# clock_led_switches.net
KiCad netlist of a schematic drawn in Altium Designer
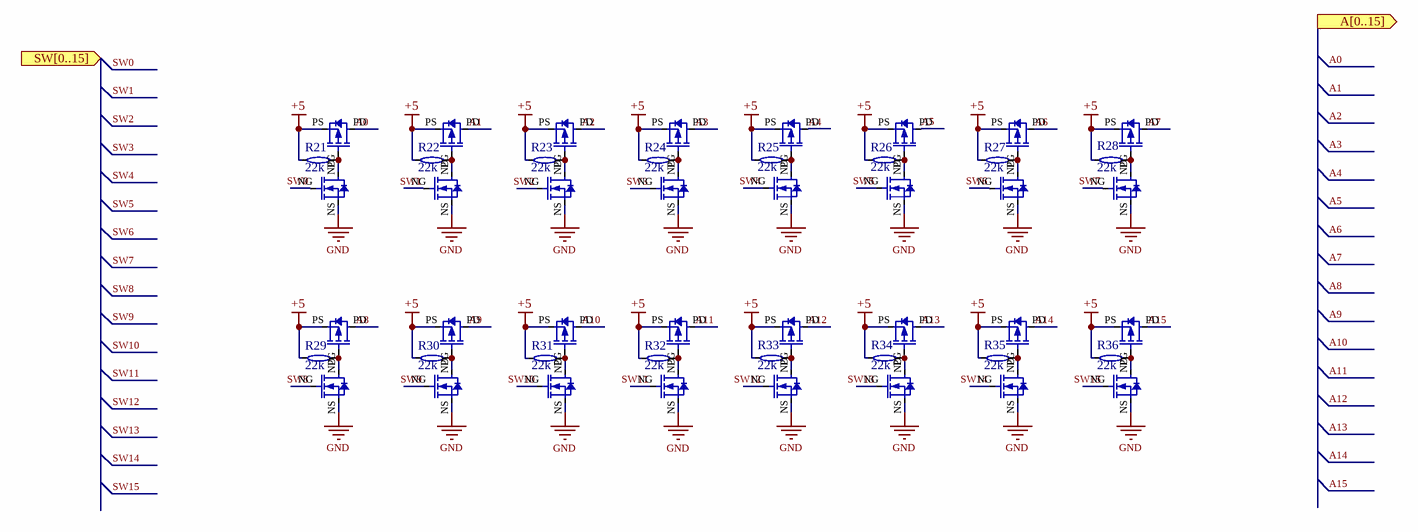
[diagram p0: clock_led_switches.SchDoc]

(export (version "E")
  (design (tool "Eeschema 10.0.6"))
  (components
    (comp (ref "Q1")
      (value "PJSEMI_PJM05C20DFA")
      (footprint "DFN-6")
      (description "Dual N/P Mofset")
      (libsource (lib "clock_led") (part "PJSEMI_PJM05C20DFA"))
    )
    (comp (ref "Q2")
      (value "PJSEMI_PJM05C20DFA")
      (footprint "DFN-6")
      (description "Dual N/P Mofset")
      (libsource (lib "clock_led") (part "PJSEMI_PJM05C20DFA"))
    )
    (comp (ref "Q3")
      (value "PJSEMI_PJM05C20DFA")
      (footprint "DFN-6")
      (description "Dual N/P Mofset")
      (libsource (lib "clock_led") (part "PJSEMI_PJM05C20DFA"))
    )
    (comp (ref "Q4")
      (value "PJSEMI_PJM05C20DFA")
      (footprint "DFN-6")
      (description "Dual N/P Mofset")
      (libsource (lib "clock_led") (part "PJSEMI_PJM05C20DFA"))
    )
    (comp (ref "Q5")
      (value "PJSEMI_PJM05C20DFA")
      (footprint "DFN-6")
      (description "Dual N/P Mofset")
      (libsource (lib "clock_led") (part "PJSEMI_PJM05C20DFA"))
    )
    (comp (ref "Q6")
      (value "PJSEMI_PJM05C20DFA")
      (footprint "DFN-6")
      (description "Dual N/P Mofset")
      (libsource (lib "clock_led") (part "PJSEMI_PJM05C20DFA"))
    )
    (comp (ref "Q7")
      (value "PJSEMI_PJM05C20DFA")
      (footprint "DFN-6")
      (description "Dual N/P Mofset")
      (libsource (lib "clock_led") (part "PJSEMI_PJM05C20DFA"))
    )
    (comp (ref "Q8")
      (value "PJSEMI_PJM05C20DFA")
      (footprint "DFN-6")
      (description "Dual N/P Mofset")
      (libsource (lib "") (part "PJSEMI_PJM05C20DFA_2"))
    )
    (comp (ref "Q9")
      (value "PJSEMI_PJM05C20DFA")
      (footprint "DFN-6")
      (description "Dual N/P Mofset")
      (libsource (lib "clock_led") (part "PJSEMI_PJM05C20DFA"))
    )
    (comp (ref "Q10")
      (value "PJSEMI_PJM05C20DFA")
      (footprint "DFN-6")
      (description "Dual N/P Mofset")
      (libsource (lib "clock_led") (part "PJSEMI_PJM05C20DFA"))
    )
    (comp (ref "Q11")
      (value "PJSEMI_PJM05C20DFA")
      (footprint "DFN-6")
      (description "Dual N/P Mofset")
      (libsource (lib "clock_led") (part "PJSEMI_PJM05C20DFA"))
    )
    (comp (ref "Q12")
      (value "PJSEMI_PJM05C20DFA")
      (footprint "DFN-6")
      (description "Dual N/P Mofset")
      (libsource (lib "clock_led") (part "PJSEMI_PJM05C20DFA"))
    )
    (comp (ref "Q13")
      (value "PJSEMI_PJM05C20DFA")
      (footprint "DFN-6")
      (description "Dual N/P Mofset")
      (libsource (lib "clock_led") (part "PJSEMI_PJM05C20DFA"))
    )
    (comp (ref "Q14")
      (value "PJSEMI_PJM05C20DFA")
      (footprint "DFN-6")
      (description "Dual N/P Mofset")
      (libsource (lib "clock_led") (part "PJSEMI_PJM05C20DFA"))
    )
    (comp (ref "Q15")
      (value "PJSEMI_PJM05C20DFA")
      (footprint "DFN-6")
      (description "Dual N/P Mofset")
      (libsource (lib "clock_led") (part "PJSEMI_PJM05C20DFA"))
    )
    (comp (ref "Q16")
      (value "PJSEMI_PJM05C20DFA")
      (footprint "DFN-6")
      (description "Dual N/P Mofset")
      (libsource (lib "clock_led") (part "PJSEMI_PJM05C20DFA"))
    )
    (comp (ref "R21")
      (value "22k")
      (footprint "RES 0402_1005 RF")
      (description "Chip Resistor")
      (libsource (lib "clock_led") (part "RES_0402_22k"))
    )
    (comp (ref "R22")
      (value "22k")
      (footprint "RES 0402_1005 RF")
      (description "Chip Resistor")
      (libsource (lib "clock_led") (part "RES_0402_22k"))
    )
    (comp (ref "R23")
      (value "22k")
      (footprint "RES 0402_1005 RF")
      (description "Chip Resistor")
      (libsource (lib "clock_led") (part "RES_0402_22k"))
    )
    (comp (ref "R24")
      (value "22k")
      (footprint "RES 0402_1005 RF")
      (description "Chip Resistor")
      (libsource (lib "clock_led") (part "RES_0402_22k"))
    )
    (comp (ref "R25")
      (value "22k")
      (footprint "RES 0402_1005 RF")
      (description "Chip Resistor")
      (libsource (lib "clock_led") (part "RES_0402_22k"))
    )
    (comp (ref "R26")
      (value "22k")
      (footprint "RES 0402_1005 RF")
      (description "Chip Resistor")
      (libsource (lib "clock_led") (part "RES_0402_22k"))
    )
    (comp (ref "R27")
      (value "22k")
      (footprint "RES 0402_1005 RF")
      (description "Chip Resistor")
      (libsource (lib "clock_led") (part "RES_0402_22k"))
    )
    (comp (ref "R28")
      (value "22k")
      (footprint "RES 0402_1005 RF")
      (description "Chip Resistor")
      (libsource (lib "clock_led") (part "RES_0402_22k"))
    )
    (comp (ref "R29")
      (value "22k")
      (footprint "RES 0402_1005 RF")
      (description "Chip Resistor")
      (libsource (lib "clock_led") (part "RES_0402_22k"))
    )
    (comp (ref "R30")
      (value "22k")
      (footprint "RES 0402_1005 RF")
      (description "Chip Resistor")
      (libsource (lib "clock_led") (part "RES_0402_22k"))
    )
    (comp (ref "R31")
      (value "22k")
      (footprint "RES 0402_1005 RF")
      (description "Chip Resistor")
      (libsource (lib "clock_led") (part "RES_0402_22k"))
    )
    (comp (ref "R32")
      (value "22k")
      (footprint "RES 0402_1005 RF")
      (description "Chip Resistor")
      (libsource (lib "clock_led") (part "RES_0402_22k"))
    )
    (comp (ref "R33")
      (value "22k")
      (footprint "RES 0402_1005 RF")
      (description "Chip Resistor")
      (libsource (lib "clock_led") (part "RES_0402_22k"))
    )
    (comp (ref "R34")
      (value "22k")
      (footprint "RES 0402_1005 RF")
      (description "Chip Resistor")
      (libsource (lib "clock_led") (part "RES_0402_22k"))
    )
    (comp (ref "R35")
      (value "22k")
      (footprint "RES 0402_1005 RF")
      (description "Chip Resistor")
      (libsource (lib "clock_led") (part "RES_0402_22k"))
    )
    (comp (ref "R36")
      (value "22k")
      (footprint "RES 0402_1005 RF")
      (description "Chip Resistor")
      (libsource (lib "clock_led") (part "RES_0402_22k"))
    )
  )
  (nets
    (net (code "1") (name "+5") (class "Default")
      (node (ref "Q1") (pin "PS") (pinfunction "PS_PS") (pintype "passive"))
      (node (ref "Q10") (pin "PS") (pinfunction "PS_PS") (pintype "passive"))
      (node (ref "Q11") (pin "PS") (pinfunction "PS_PS") (pintype "passive"))
      (node (ref "Q12") (pin "PS") (pinfunction "PS_PS") (pintype "passive"))
      (node (ref "Q13") (pin "PS") (pinfunction "PS_PS") (pintype "passive"))
      (node (ref "Q14") (pin "PS") (pinfunction "PS_PS") (pintype "passive"))
      (node (ref "Q15") (pin "PS") (pinfunction "PS_PS") (pintype "passive"))
      (node (ref "Q16") (pin "PS") (pinfunction "PS_PS") (pintype "passive"))
      (node (ref "Q2") (pin "PS") (pinfunction "PS_PS") (pintype "passive"))
      (node (ref "Q3") (pin "PS") (pinfunction "PS_PS") (pintype "passive"))
      (node (ref "Q4") (pin "PS") (pinfunction "PS_PS") (pintype "passive"))
      (node (ref "Q5") (pin "PS") (pinfunction "PS_PS") (pintype "passive"))
      (node (ref "Q6") (pin "PS") (pinfunction "PS_PS") (pintype "passive"))
      (node (ref "Q7") (pin "PS") (pinfunction "PS_PS") (pintype "passive"))
      (node (ref "Q8") (pin "PS") (pinfunction "PS_PS") (pintype "passive"))
      (node (ref "Q9") (pin "PS") (pinfunction "PS_PS") (pintype "passive"))
      (node (ref "R21") (pin "1") (pinfunction "1_1") (pintype "passive"))
      (node (ref "R22") (pin "1") (pinfunction "1_1") (pintype "passive"))
      (node (ref "R23") (pin "1") (pinfunction "1_1") (pintype "passive"))
      (node (ref "R24") (pin "1") (pinfunction "1_1") (pintype "passive"))
      (node (ref "R25") (pin "1") (pinfunction "1_1") (pintype "passive"))
      (node (ref "R26") (pin "1") (pinfunction "1_1") (pintype "passive"))
      (node (ref "R27") (pin "1") (pinfunction "1_1") (pintype "passive"))
      (node (ref "R28") (pin "1") (pinfunction "1_1") (pintype "passive"))
      (node (ref "R29") (pin "1") (pinfunction "1_1") (pintype "passive"))
      (node (ref "R30") (pin "1") (pinfunction "1_1") (pintype "passive"))
      (node (ref "R31") (pin "1") (pinfunction "1_1") (pintype "passive"))
      (node (ref "R32") (pin "1") (pinfunction "1_1") (pintype "passive"))
      (node (ref "R33") (pin "1") (pinfunction "1_1") (pintype "passive"))
      (node (ref "R34") (pin "1") (pinfunction "1_1") (pintype "passive"))
      (node (ref "R35") (pin "1") (pinfunction "1_1") (pintype "passive"))
      (node (ref "R36") (pin "1") (pinfunction "1_1") (pintype "passive"))
    )
    (net (code "2") (name "/A0") (class "Default")
      (node (ref "Q1") (pin "PD") (pinfunction "PD_PD") (pintype "passive"))
    )
    (net (code "3") (name "/A1") (class "Default")
      (node (ref "Q2") (pin "PD") (pinfunction "PD_PD") (pintype "passive"))
    )
    (net (code "4") (name "/A2") (class "Default")
      (node (ref "Q3") (pin "PD") (pinfunction "PD_PD") (pintype "passive"))
    )
    (net (code "5") (name "/A3") (class "Default")
      (node (ref "Q4") (pin "PD") (pinfunction "PD_PD") (pintype "passive"))
    )
    (net (code "6") (name "/A4") (class "Default")
      (node (ref "Q5") (pin "PD") (pinfunction "PD_PD") (pintype "passive"))
    )
    (net (code "7") (name "/A5") (class "Default")
      (node (ref "Q6") (pin "PD") (pinfunction "PD_PD") (pintype "passive"))
    )
    (net (code "8") (name "/A6") (class "Default")
      (node (ref "Q7") (pin "PD") (pinfunction "PD_PD") (pintype "passive"))
    )
    (net (code "9") (name "/A7") (class "Default")
      (node (ref "Q8") (pin "PD") (pinfunction "PD_PD") (pintype "passive"))
    )
    (net (code "10") (name "/A8") (class "Default")
      (node (ref "Q9") (pin "PD") (pinfunction "PD_PD") (pintype "passive"))
    )
    (net (code "11") (name "/A9") (class "Default")
      (node (ref "Q10") (pin "PD") (pinfunction "PD_PD") (pintype "passive"))
    )
    (net (code "12") (name "/A10") (class "Default")
      (node (ref "Q11") (pin "PD") (pinfunction "PD_PD") (pintype "passive"))
    )
    (net (code "13") (name "/A11") (class "Default")
      (node (ref "Q12") (pin "PD") (pinfunction "PD_PD") (pintype "passive"))
    )
    (net (code "14") (name "/A12") (class "Default")
      (node (ref "Q13") (pin "PD") (pinfunction "PD_PD") (pintype "passive"))
    )
    (net (code "15") (name "/A13") (class "Default")
      (node (ref "Q14") (pin "PD") (pinfunction "PD_PD") (pintype "passive"))
    )
    (net (code "16") (name "/A14") (class "Default")
      (node (ref "Q15") (pin "PD") (pinfunction "PD_PD") (pintype "passive"))
    )
    (net (code "17") (name "/A15") (class "Default")
      (node (ref "Q16") (pin "PD") (pinfunction "PD_PD") (pintype "passive"))
    )
    (net (code "19") (name "/SW0") (class "Default")
      (node (ref "Q1") (pin "NG") (pinfunction "NG_NG") (pintype "passive"))
    )
    (net (code "20") (name "/SW1") (class "Default")
      (node (ref "Q2") (pin "NG") (pinfunction "NG_NG") (pintype "passive"))
    )
    (net (code "21") (name "/SW2") (class "Default")
      (node (ref "Q3") (pin "NG") (pinfunction "NG_NG") (pintype "passive"))
    )
    (net (code "22") (name "/SW3") (class "Default")
      (node (ref "Q4") (pin "NG") (pinfunction "NG_NG") (pintype "passive"))
    )
    (net (code "23") (name "/SW4") (class "Default")
      (node (ref "Q5") (pin "NG") (pinfunction "NG_NG") (pintype "passive"))
    )
    (net (code "24") (name "/SW5") (class "Default")
      (node (ref "Q6") (pin "NG") (pinfunction "NG_NG") (pintype "passive"))
    )
    (net (code "25") (name "/SW6") (class "Default")
      (node (ref "Q7") (pin "NG") (pinfunction "NG_NG") (pintype "passive"))
    )
    (net (code "26") (name "/SW7") (class "Default")
      (node (ref "Q8") (pin "NG") (pinfunction "NG_NG") (pintype "passive"))
    )
    (net (code "27") (name "/SW8") (class "Default")
      (node (ref "Q9") (pin "NG") (pinfunction "NG_NG") (pintype "passive"))
    )
    (net (code "28") (name "/SW9") (class "Default")
      (node (ref "Q10") (pin "NG") (pinfunction "NG_NG") (pintype "passive"))
    )
    (net (code "29") (name "/SW10") (class "Default")
      (node (ref "Q11") (pin "NG") (pinfunction "NG_NG") (pintype "passive"))
    )
    (net (code "30") (name "/SW11") (class "Default")
      (node (ref "Q12") (pin "NG") (pinfunction "NG_NG") (pintype "passive"))
    )
    (net (code "31") (name "/SW12") (class "Default")
      (node (ref "Q13") (pin "NG") (pinfunction "NG_NG") (pintype "passive"))
    )
    (net (code "32") (name "/SW13") (class "Default")
      (node (ref "Q14") (pin "NG") (pinfunction "NG_NG") (pintype "passive"))
    )
    (net (code "33") (name "/SW14") (class "Default")
      (node (ref "Q15") (pin "NG") (pinfunction "NG_NG") (pintype "passive"))
    )
    (net (code "34") (name "/SW15") (class "Default")
      (node (ref "Q16") (pin "NG") (pinfunction "NG_NG") (pintype "passive"))
    )
    (net (code "36") (name "GND") (class "Default")
      (node (ref "Q1") (pin "NS") (pinfunction "NS_NS") (pintype "passive"))
      (node (ref "Q10") (pin "NS") (pinfunction "NS_NS") (pintype "passive"))
      (node (ref "Q11") (pin "NS") (pinfunction "NS_NS") (pintype "passive"))
      (node (ref "Q12") (pin "NS") (pinfunction "NS_NS") (pintype "passive"))
      (node (ref "Q13") (pin "NS") (pinfunction "NS_NS") (pintype "passive"))
      (node (ref "Q14") (pin "NS") (pinfunction "NS_NS") (pintype "passive"))
      (node (ref "Q15") (pin "NS") (pinfunction "NS_NS") (pintype "passive"))
      (node (ref "Q16") (pin "NS") (pinfunction "NS_NS") (pintype "passive"))
      (node (ref "Q2") (pin "NS") (pinfunction "NS_NS") (pintype "passive"))
      (node (ref "Q3") (pin "NS") (pinfunction "NS_NS") (pintype "passive"))
      (node (ref "Q4") (pin "NS") (pinfunction "NS_NS") (pintype "passive"))
      (node (ref "Q5") (pin "NS") (pinfunction "NS_NS") (pintype "passive"))
      (node (ref "Q6") (pin "NS") (pinfunction "NS_NS") (pintype "passive"))
      (node (ref "Q7") (pin "NS") (pinfunction "NS_NS") (pintype "passive"))
      (node (ref "Q8") (pin "NS") (pinfunction "NS_NS") (pintype "passive"))
      (node (ref "Q9") (pin "NS") (pinfunction "NS_NS") (pintype "passive"))
    )
    (net (code "37") (name "Net-(Q1-PadND)") (class "Default")
      (node (ref "Q1") (pin "ND") (pinfunction "ND_ND") (pintype "passive"))
      (node (ref "Q1") (pin "PG") (pinfunction "PG_PG") (pintype "passive"))
      (node (ref "R21") (pin "2") (pinfunction "2_2") (pintype "passive"))
    )
    (net (code "38") (name "Net-(Q2-PadND)") (class "Default")
      (node (ref "Q2") (pin "ND") (pinfunction "ND_ND") (pintype "passive"))
      (node (ref "Q2") (pin "PG") (pinfunction "PG_PG") (pintype "passive"))
      (node (ref "R22") (pin "2") (pinfunction "2_2") (pintype "passive"))
    )
    (net (code "39") (name "Net-(Q3-PadND)") (class "Default")
      (node (ref "Q3") (pin "ND") (pinfunction "ND_ND") (pintype "passive"))
      (node (ref "Q3") (pin "PG") (pinfunction "PG_PG") (pintype "passive"))
      (node (ref "R23") (pin "2") (pinfunction "2_2") (pintype "passive"))
    )
    (net (code "40") (name "Net-(Q4-PadND)") (class "Default")
      (node (ref "Q4") (pin "ND") (pinfunction "ND_ND") (pintype "passive"))
      (node (ref "Q4") (pin "PG") (pinfunction "PG_PG") (pintype "passive"))
      (node (ref "R24") (pin "2") (pinfunction "2_2") (pintype "passive"))
    )
    (net (code "41") (name "Net-(Q5-PadND)") (class "Default")
      (node (ref "Q5") (pin "ND") (pinfunction "ND_ND") (pintype "passive"))
      (node (ref "Q5") (pin "PG") (pinfunction "PG_PG") (pintype "passive"))
      (node (ref "R25") (pin "2") (pinfunction "2_2") (pintype "passive"))
    )
    (net (code "42") (name "Net-(Q6-PadND)") (class "Default")
      (node (ref "Q6") (pin "ND") (pinfunction "ND_ND") (pintype "passive"))
      (node (ref "Q6") (pin "PG") (pinfunction "PG_PG") (pintype "passive"))
      (node (ref "R26") (pin "2") (pinfunction "2_2") (pintype "passive"))
    )
    (net (code "43") (name "Net-(Q7-PadND)") (class "Default")
      (node (ref "Q7") (pin "ND") (pinfunction "ND_ND") (pintype "passive"))
      (node (ref "Q7") (pin "PG") (pinfunction "PG_PG") (pintype "passive"))
      (node (ref "R27") (pin "2") (pinfunction "2_2") (pintype "passive"))
    )
    (net (code "44") (name "Net-(Q8-PadND)") (class "Default")
      (node (ref "Q8") (pin "ND") (pinfunction "ND_ND") (pintype "passive"))
      (node (ref "Q8") (pin "PG") (pinfunction "PG_PG") (pintype "passive"))
      (node (ref "R28") (pin "2") (pinfunction "2_2") (pintype "passive"))
    )
    (net (code "45") (name "Net-(Q9-PadND)") (class "Default")
      (node (ref "Q9") (pin "ND") (pinfunction "ND_ND") (pintype "passive"))
      (node (ref "Q9") (pin "PG") (pinfunction "PG_PG") (pintype "passive"))
      (node (ref "R29") (pin "2") (pinfunction "2_2") (pintype "passive"))
    )
    (net (code "46") (name "Net-(Q10-PadND)") (class "Default")
      (node (ref "Q10") (pin "ND") (pinfunction "ND_ND") (pintype "passive"))
      (node (ref "Q10") (pin "PG") (pinfunction "PG_PG") (pintype "passive"))
      (node (ref "R30") (pin "2") (pinfunction "2_2") (pintype "passive"))
    )
    (net (code "47") (name "Net-(Q11-PadND)") (class "Default")
      (node (ref "Q11") (pin "ND") (pinfunction "ND_ND") (pintype "passive"))
      (node (ref "Q11") (pin "PG") (pinfunction "PG_PG") (pintype "passive"))
      (node (ref "R31") (pin "2") (pinfunction "2_2") (pintype "passive"))
    )
    (net (code "48") (name "Net-(Q12-PadND)") (class "Default")
      (node (ref "Q12") (pin "ND") (pinfunction "ND_ND") (pintype "passive"))
      (node (ref "Q12") (pin "PG") (pinfunction "PG_PG") (pintype "passive"))
      (node (ref "R32") (pin "2") (pinfunction "2_2") (pintype "passive"))
    )
    (net (code "49") (name "Net-(Q13-PadND)") (class "Default")
      (node (ref "Q13") (pin "ND") (pinfunction "ND_ND") (pintype "passive"))
      (node (ref "Q13") (pin "PG") (pinfunction "PG_PG") (pintype "passive"))
      (node (ref "R33") (pin "2") (pinfunction "2_2") (pintype "passive"))
    )
    (net (code "50") (name "Net-(Q14-PadND)") (class "Default")
      (node (ref "Q14") (pin "ND") (pinfunction "ND_ND") (pintype "passive"))
      (node (ref "Q14") (pin "PG") (pinfunction "PG_PG") (pintype "passive"))
      (node (ref "R34") (pin "2") (pinfunction "2_2") (pintype "passive"))
    )
    (net (code "51") (name "Net-(Q15-PadND)") (class "Default")
      (node (ref "Q15") (pin "ND") (pinfunction "ND_ND") (pintype "passive"))
      (node (ref "Q15") (pin "PG") (pinfunction "PG_PG") (pintype "passive"))
      (node (ref "R35") (pin "2") (pinfunction "2_2") (pintype "passive"))
    )
    (net (code "52") (name "Net-(Q16-PadND)") (class "Default")
      (node (ref "Q16") (pin "ND") (pinfunction "ND_ND") (pintype "passive"))
      (node (ref "Q16") (pin "PG") (pinfunction "PG_PG") (pintype "passive"))
      (node (ref "R36") (pin "2") (pinfunction "2_2") (pintype "passive"))
    )
  )
)
